# WemosD1_Control.net
KiCad netlist of a schematic drawn in EAGLE
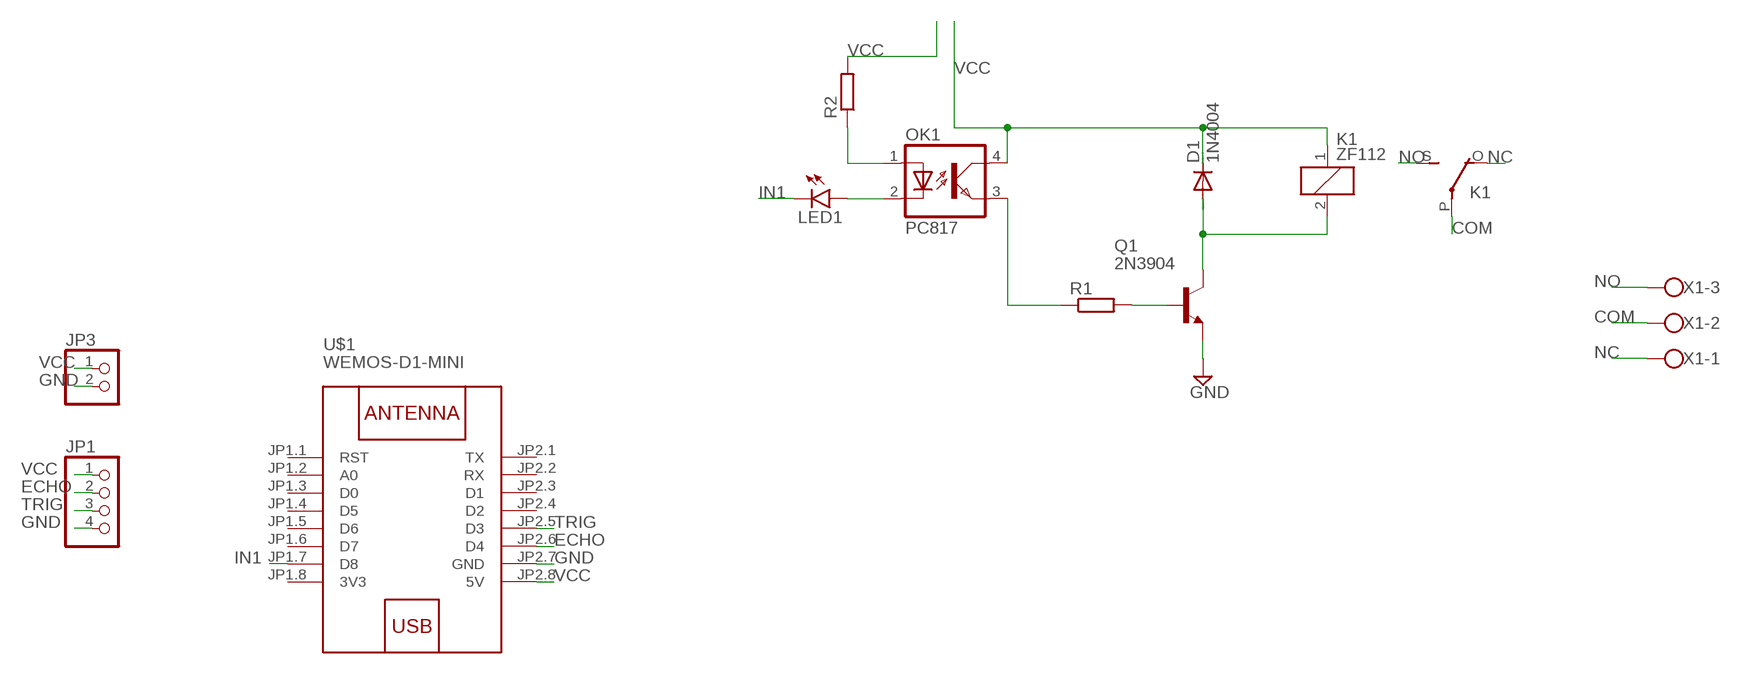
[diagram p0: schematic, sheet 1]

(export (version "E")
  (design (tool "Eeschema 10.0.6"))
  (components
    (comp (ref "D1")
      (value "1N4004")
      (footprint "eagle-import:DO41-10")
      (libsource (lib "eagle-import") (part "1N4004"))
    )
    (comp (ref "JP1")
      (value "PINHD-1X4")
      (footprint "eagle-import:1X04")
      (libsource (lib "eagle-import") (part "PINHD-1X4"))
    )
    (comp (ref "JP3")
      (value "PINHD-1X2")
      (footprint "eagle-import:1X02")
      (libsource (lib "eagle-import") (part "PINHD-1X2"))
    )
    (comp (ref "K1")
      (value "ZF112")
      (footprint "eagle-import:ZF112")
      (libsource (lib "eagle-import") (part "ZF112"))
    )
    (comp (ref "LED1")
      (value "LED3MM")
      (footprint "eagle-import:LED3MM")
      (libsource (lib "eagle-import") (part "LED3MM"))
    )
    (comp (ref "OK1")
      (value "PC817")
      (footprint "eagle-import:DIL04")
      (fields (field (name "MPN") "PC817X4J000F"))
      (libsource (lib "eagle-import") (part "PC817"))
    )
    (comp (ref "Q1")
      (value "2N3904")
      (footprint "eagle-import:TO92")
      (libsource (lib "eagle-import") (part "2N3904"))
    )
    (comp (ref "R1")
      (value "R-EU_0204/7")
      (footprint "eagle-import:0204_7")
      (libsource (lib "eagle-import") (part "R-EU_0204/7"))
    )
    (comp (ref "R2")
      (value "R-EU_0204/7")
      (footprint "eagle-import:0204_7")
      (libsource (lib "eagle-import") (part "R-EU_0204/7"))
    )
    (comp (ref "U$1")
      (value "WEMOS-D1-MINI")
      (footprint "eagle-import:WEMOS-D1-MINI")
      (libsource (lib "eagle-import") (part "WEMOS-D1-MINI"))
    )
    (comp (ref "X1")
      (value "W237-103")
      (footprint "eagle-import:W237-103")
      (fields (field (name "MPN") "237-103"))
      (libsource (lib "eagle-import") (part "W237-103"))
    )
  )
  (nets
    (net (code "1") (name "/3V3") (class "Default")
      (node (ref "U$1") (pin "JP1.8") (pinfunction "3V3_JP1.8") (pintype "power_in"))
    )
    (net (code "2") (name "/COM") (class "Default")
      (node (ref "K1") (pin "P") (pinfunction "P_P") (pintype "passive"))
      (node (ref "X1") (pin "2") (pinfunction "KL_2") (pintype "passive"))
    )
    (net (code "3") (name "/ECHO") (class "Default")
      (node (ref "JP1") (pin "2") (pinfunction "2_2") (pintype "passive"))
      (node (ref "U$1") (pin "JP2.6") (pinfunction "D4_JP2.6") (pintype "bidirectional"))
    )
    (net (code "4") (name "/IN1") (class "Default")
      (node (ref "LED1") (pin "K") (pinfunction "C_K") (pintype "passive"))
      (node (ref "U$1") (pin "JP1.7") (pinfunction "D8_JP1.7") (pintype "bidirectional"))
    )
    (net (code "5") (name "/NC") (class "Default")
      (node (ref "K1") (pin "O") (pinfunction "O_O") (pintype "passive"))
      (node (ref "X1") (pin "1") (pinfunction "KL_1") (pintype "passive"))
    )
    (net (code "6") (name "/NO") (class "Default")
      (node (ref "K1") (pin "S") (pinfunction "S_S") (pintype "passive"))
      (node (ref "X1") (pin "3") (pinfunction "KL_3") (pintype "passive"))
    )
    (net (code "7") (name "/TRIG") (class "Default")
      (node (ref "JP1") (pin "3") (pinfunction "3_3") (pintype "passive"))
      (node (ref "U$1") (pin "JP2.5") (pinfunction "D3_JP2.5") (pintype "bidirectional"))
    )
    (net (code "8") (name "/VCC") (class "Default")
      (node (ref "D1") (pin "C") (pinfunction "C_C") (pintype "passive"))
      (node (ref "JP1") (pin "1") (pinfunction "1_1") (pintype "passive"))
      (node (ref "JP3") (pin "1") (pinfunction "1_1") (pintype "passive"))
      (node (ref "K1") (pin "1") (pinfunction "1_1") (pintype "passive"))
      (node (ref "OK1") (pin "4") (pinfunction "COL_4") (pintype "passive"))
      (node (ref "R2") (pin "2") (pinfunction "2_2") (pintype "passive"))
      (node (ref "U$1") (pin "JP2.8") (pinfunction "5V_JP2.8") (pintype "power_in"))
    )
    (net (code "9") (name "GND") (class "Default")
      (node (ref "JP1") (pin "4") (pinfunction "4_4") (pintype "passive"))
      (node (ref "JP3") (pin "2") (pinfunction "2_2") (pintype "passive"))
      (node (ref "Q1") (pin "3") (pinfunction "E_3") (pintype "passive"))
      (node (ref "U$1") (pin "JP2.7") (pinfunction "GND_JP2.7") (pintype "power_in"))
    )
    (net (code "10") (name "Net-(OK1-A)") (class "Default")
      (node (ref "OK1") (pin "1") (pinfunction "A_1") (pintype "passive"))
      (node (ref "R2") (pin "1") (pinfunction "1_1") (pintype "passive"))
    )
    (net (code "11") (name "Net-(OK1-C)") (class "Default")
      (node (ref "LED1") (pin "A") (pinfunction "A_A") (pintype "passive"))
      (node (ref "OK1") (pin "2") (pinfunction "C_2") (pintype "passive"))
    )
    (net (code "12") (name "Net-(OK1-EMIT)") (class "Default")
      (node (ref "OK1") (pin "3") (pinfunction "EMIT_3") (pintype "passive"))
      (node (ref "R1") (pin "1") (pinfunction "1_1") (pintype "passive"))
    )
    (net (code "13") (name "Net-(Q1-B)") (class "Default")
      (node (ref "Q1") (pin "2") (pinfunction "B_2") (pintype "passive"))
      (node (ref "R1") (pin "2") (pinfunction "2_2") (pintype "passive"))
    )
    (net (code "14") (name "Net-(Q1-C)") (class "Default")
      (node (ref "D1") (pin "A") (pinfunction "A_A") (pintype "passive"))
      (node (ref "K1") (pin "2") (pinfunction "2_2") (pintype "passive"))
      (node (ref "Q1") (pin "1") (pinfunction "C_1") (pintype "passive"))
    )
    (net (code "15") (name "unconnected-(U$1-A0-PadJP1.2)") (class "Default")
      (node (ref "U$1") (pin "JP1.2") (pinfunction "A0_JP1.2") (pintype "bidirectional"))
    )
    (net (code "16") (name "unconnected-(U$1-D0-PadJP1.3)") (class "Default")
      (node (ref "U$1") (pin "JP1.3") (pinfunction "D0_JP1.3") (pintype "bidirectional"))
    )
    (net (code "17") (name "unconnected-(U$1-D1-PadJP2.3)") (class "Default")
      (node (ref "U$1") (pin "JP2.3") (pinfunction "D1_JP2.3") (pintype "bidirectional"))
    )
    (net (code "18") (name "unconnected-(U$1-D2-PadJP2.4)") (class "Default")
      (node (ref "U$1") (pin "JP2.4") (pinfunction "D2_JP2.4") (pintype "bidirectional"))
    )
    (net (code "19") (name "unconnected-(U$1-D5-PadJP1.4)") (class "Default")
      (node (ref "U$1") (pin "JP1.4") (pinfunction "D5_JP1.4") (pintype "bidirectional"))
    )
    (net (code "20") (name "unconnected-(U$1-D6-PadJP1.5)") (class "Default")
      (node (ref "U$1") (pin "JP1.5") (pinfunction "D6_JP1.5") (pintype "bidirectional"))
    )
    (net (code "21") (name "unconnected-(U$1-D7-PadJP1.6)") (class "Default")
      (node (ref "U$1") (pin "JP1.6") (pinfunction "D7_JP1.6") (pintype "bidirectional"))
    )
    (net (code "22") (name "unconnected-(U$1-RST-PadJP1.1)") (class "Default")
      (node (ref "U$1") (pin "JP1.1") (pinfunction "RST_JP1.1") (pintype "bidirectional"))
    )
    (net (code "23") (name "unconnected-(U$1-RX-PadJP2.2)") (class "Default")
      (node (ref "U$1") (pin "JP2.2") (pinfunction "RX_JP2.2") (pintype "bidirectional"))
    )
    (net (code "24") (name "unconnected-(U$1-TX-PadJP2.1)") (class "Default")
      (node (ref "U$1") (pin "JP2.1") (pinfunction "TX_JP2.1") (pintype "bidirectional"))
    )
  )
)
